# Display.net
KiCad netlist of a schematic drawn in Altium Designer
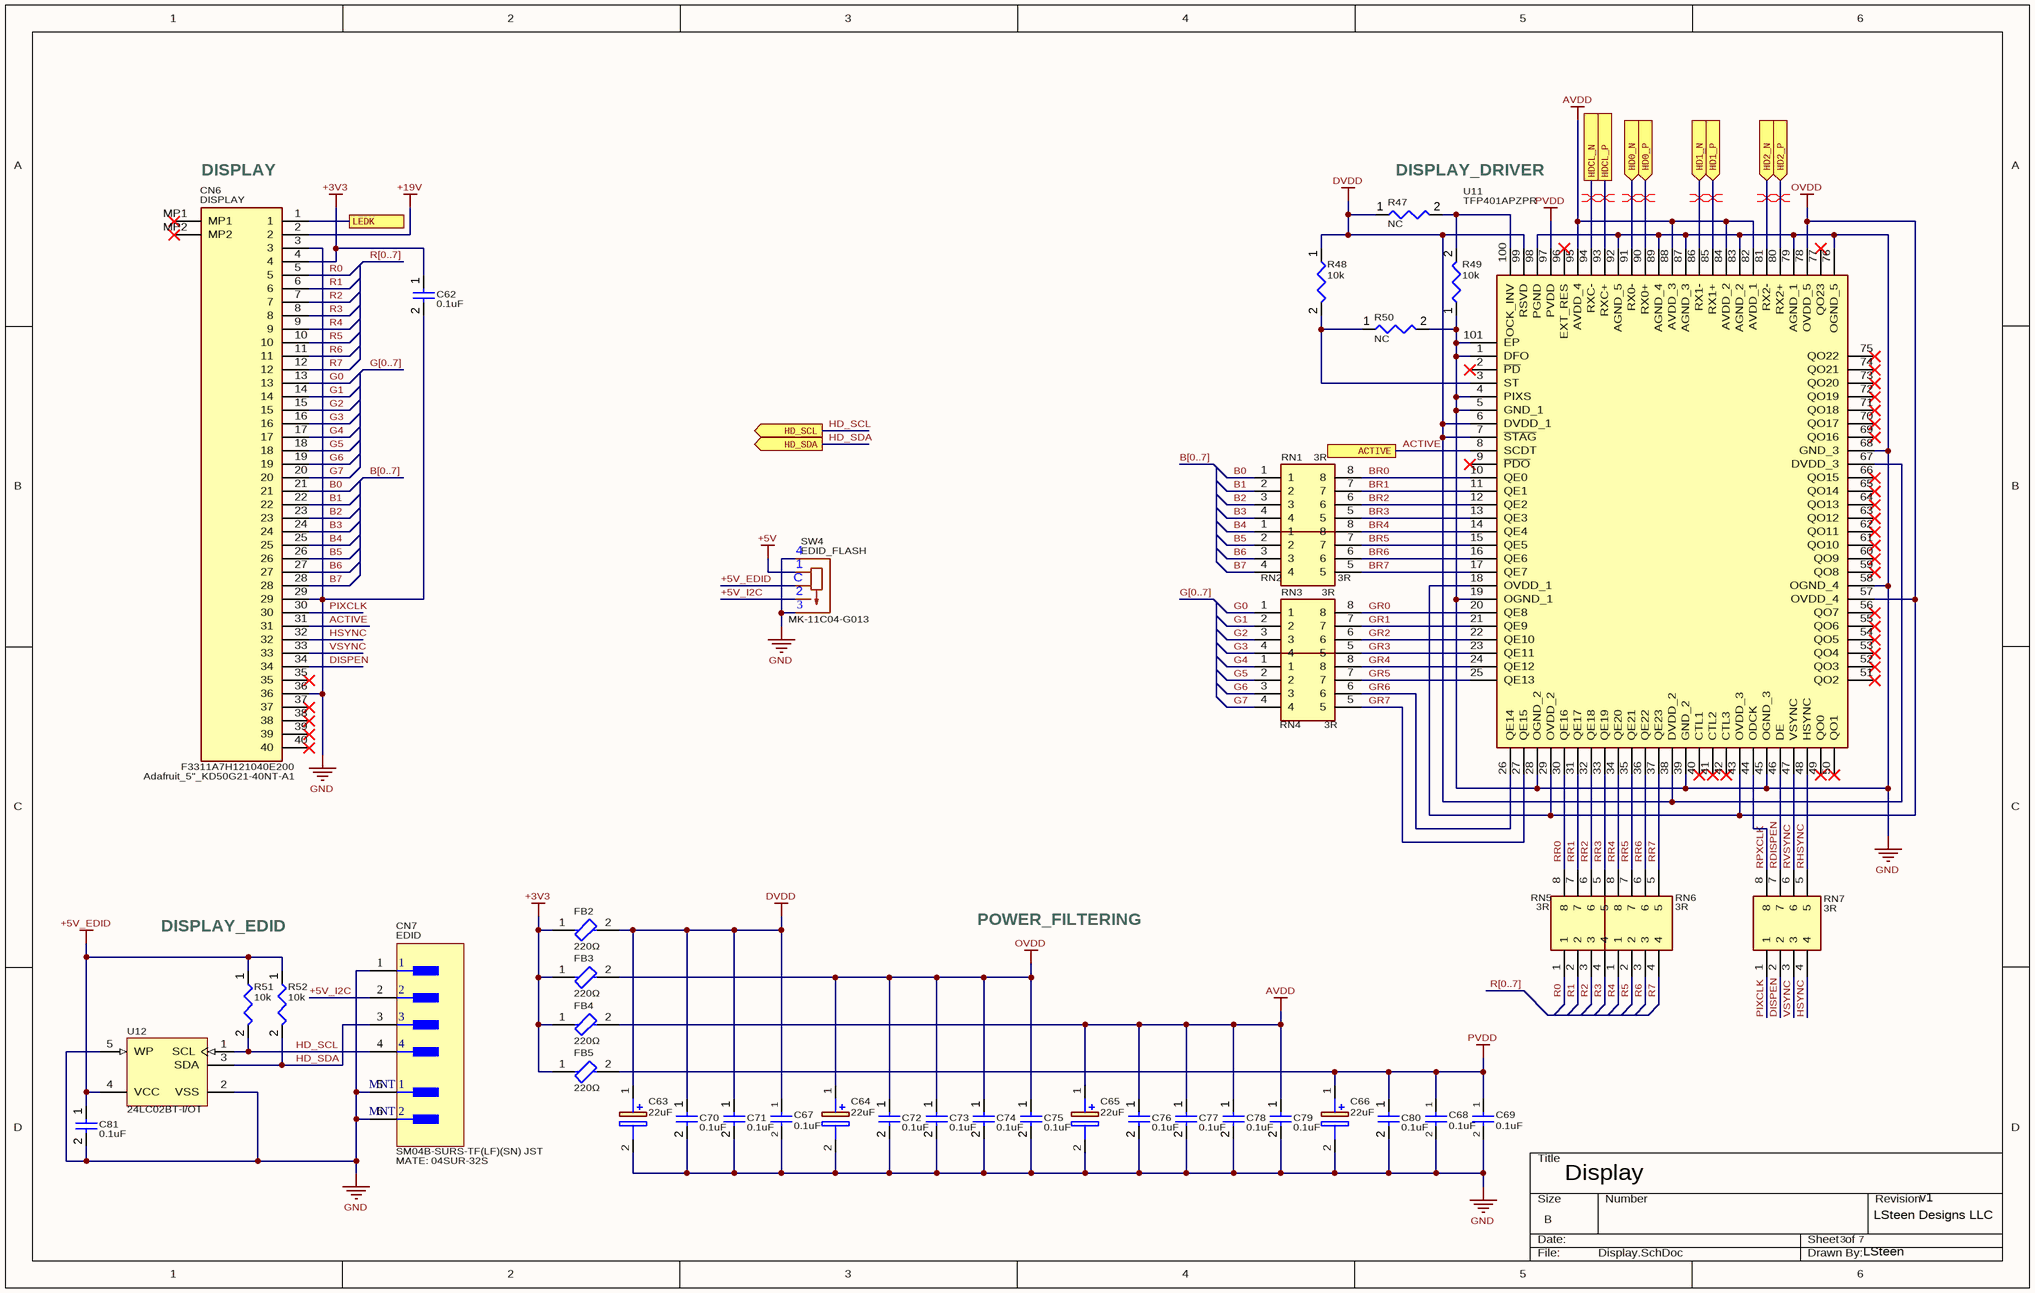
[diagram p0: Display.SchDoc]

(export (version "E")
  (design (tool "Eeschema 10.0.6"))
  (components
    (comp (ref "C62")
      (value "0.1uF")
      (footprint "CAPC1005X56X25LL10T15")
      (description "Chip Capacitor, 0.1 uF, +/- 5%, 16 V, 0402 (1005 Metric)")
      (fields (field (name "TOLERANCE") "5%"))
      (libsource (lib "Colorado Technical University") (part "CAP-NP-2"))
    )
    (comp (ref "C63")
      (value "22uF")
      (footprint "SamacSys:CAPPC2114X150N")
      (description "Capacitor Polarised")
      (fields
        (field (name "MANUFACTURER_PART_NUMBER") "TACR226K006XTA")
        (field (name "MOUSER PART NUMBER") "581-TACR226K006X")
      )
      (libsource (lib "SamacSys") (part "TACR226K006XTA"))
    )
    (comp (ref "C64")
      (value "22uF")
      (footprint "SamacSys:CAPPC2114X150N")
      (description "Capacitor Polarised")
      (fields
        (field (name "MANUFACTURER_PART_NUMBER") "TACR226K006XTA")
        (field (name "MOUSER PART NUMBER") "581-TACR226K006X")
      )
      (libsource (lib "SamacSys") (part "TACR226K006XTA"))
    )
    (comp (ref "C65")
      (value "22uF")
      (footprint "SamacSys:CAPPC2114X150N")
      (description "Capacitor Polarised")
      (fields
        (field (name "MANUFACTURER_PART_NUMBER") "TACR226K006XTA")
        (field (name "MOUSER PART NUMBER") "581-TACR226K006X")
      )
      (libsource (lib "SamacSys") (part "TACR226K006XTA"))
    )
    (comp (ref "C66")
      (value "22uF")
      (footprint "SamacSys:CAPPC2114X150N")
      (description "Capacitor Polarised")
      (fields
        (field (name "MANUFACTURER_PART_NUMBER") "TACR226K006XTA")
        (field (name "MOUSER PART NUMBER") "581-TACR226K006X")
      )
      (libsource (lib "SamacSys") (part "TACR226K006XTA"))
    )
    (comp (ref "C67")
      (value "0.1uF")
      (footprint "SamacSys:CAPC1005X55N")
      (description "C0402")
      (libsource (lib "SamacSys") (part "C0402"))
    )
    (comp (ref "C68")
      (value "0.1uF")
      (footprint "SamacSys:CAPC1005X55N")
      (description "C0402")
      (libsource (lib "SamacSys") (part "C0402"))
    )
    (comp (ref "C69")
      (value "0.1uF")
      (footprint "SamacSys:CAPC1005X55N")
      (description "C0402")
      (libsource (lib "SamacSys") (part "C0402"))
    )
    (comp (ref "C70")
      (value "0.1uF")
      (footprint "CAPC1005X56X25LL10T15")
      (description "Chip Capacitor, 0.1 uF, +/- 5%, 16 V, 0402 (1005 Metric)")
      (fields (field (name "TOLERANCE") "5%"))
      (libsource (lib "Colorado Technical University") (part "CAP-NP-2"))
    )
    (comp (ref "C71")
      (value "0.1uF")
      (footprint "CAPC1005X56X25LL10T15")
      (description "Chip Capacitor, 0.1 uF, +/- 5%, 16 V, 0402 (1005 Metric)")
      (fields (field (name "TOLERANCE") "5%"))
      (libsource (lib "Colorado Technical University") (part "CAP-NP-2"))
    )
    (comp (ref "C72")
      (value "0.1uF")
      (footprint "CAPC1005X56X25LL10T15")
      (description "Chip Capacitor, 0.1 uF, +/- 5%, 16 V, 0402 (1005 Metric)")
      (fields (field (name "TOLERANCE") "5%"))
      (libsource (lib "Colorado Technical University") (part "CAP-NP-2"))
    )
    (comp (ref "C73")
      (value "0.1uF")
      (footprint "CAPC1005X56X25LL10T15")
      (description "Chip Capacitor, 0.1 uF, +/- 5%, 16 V, 0402 (1005 Metric)")
      (fields (field (name "TOLERANCE") "5%"))
      (libsource (lib "Colorado Technical University") (part "CAP-NP-2"))
    )
    (comp (ref "C74")
      (value "0.1uF")
      (footprint "CAPC1005X56X25LL10T15")
      (description "Chip Capacitor, 0.1 uF, +/- 5%, 16 V, 0402 (1005 Metric)")
      (fields (field (name "TOLERANCE") "5%"))
      (libsource (lib "Colorado Technical University") (part "CAP-NP-2"))
    )
    (comp (ref "C75")
      (value "0.1uF")
      (footprint "CAPC1005X56X25LL10T15")
      (description "Chip Capacitor, 0.1 uF, +/- 5%, 16 V, 0402 (1005 Metric)")
      (fields (field (name "TOLERANCE") "5%"))
      (libsource (lib "Colorado Technical University") (part "CAP-NP-2"))
    )
    (comp (ref "C76")
      (value "0.1uF")
      (footprint "CAPC1005X56X25LL10T15")
      (description "Chip Capacitor, 0.1 uF, +/- 5%, 16 V, 0402 (1005 Metric)")
      (fields (field (name "TOLERANCE") "5%"))
      (libsource (lib "Colorado Technical University") (part "CAP-NP-2"))
    )
    (comp (ref "C77")
      (value "0.1uF")
      (footprint "CAPC1005X56X25LL10T15")
      (description "Chip Capacitor, 0.1 uF, +/- 5%, 16 V, 0402 (1005 Metric)")
      (fields (field (name "TOLERANCE") "5%"))
      (libsource (lib "Colorado Technical University") (part "CAP-NP-2"))
    )
    (comp (ref "C78")
      (value "0.1uF")
      (footprint "CAPC1005X56X25LL10T15")
      (description "Chip Capacitor, 0.1 uF, +/- 5%, 16 V, 0402 (1005 Metric)")
      (fields (field (name "TOLERANCE") "5%"))
      (libsource (lib "Colorado Technical University") (part "CAP-NP-2"))
    )
    (comp (ref "C79")
      (value "0.1uF")
      (footprint "CAPC1005X56X25LL10T15")
      (description "Chip Capacitor, 0.1 uF, +/- 5%, 16 V, 0402 (1005 Metric)")
      (fields (field (name "TOLERANCE") "5%"))
      (libsource (lib "Colorado Technical University") (part "CAP-NP-2"))
    )
    (comp (ref "C80")
      (value "0.1uF")
      (footprint "CAPC1005X56X25LL10T15")
      (description "Chip Capacitor, 0.1 uF, +/- 5%, 16 V, 0402 (1005 Metric)")
      (fields (field (name "TOLERANCE") "5%"))
      (libsource (lib "Colorado Technical University") (part "CAP-NP-2"))
    )
    (comp (ref "C81")
      (value "0.1uF")
      (footprint "CAPC1005X56X25LL10T15")
      (description "Chip Capacitor, 0.1 uF, +/- 5%, 16 V, 0402 (1005 Metric)")
      (fields (field (name "TOLERANCE") "5%"))
      (libsource (lib "Colorado Technical University") (part "CAP-NP-2"))
    )
    (comp (ref "CN6")
      (value "DISPLAY")
      (footprint "SamacSys:F3311A7H121040E200")
      (description "Connector")
      (fields (field (name "MANUFACTURER_PART_NUMBER") "F3311A7H121040E200"))
      (libsource (lib "*") (part "F3311A7H121040E200"))
    )
    (comp (ref "CN7")
      (value "EDID")
      (footprint "FP-SM04B-SURS-TF_LF_SN-MFG")
      (description "CONN HEADER SMD R/A 4POS 0.8MM")
      (libsource (lib "Altium Content Vault") (part "3b6f738a5616415d78381ad43816e4a"))
    )
    (comp (ref "FB2")
      (value "220Ω")
      (footprint "FP-BLM18-0_15-t0_5-IPC_B")
      (description "Chip Ferrite Bead, 0603, 220Ω @ 100MHz, 25%, 0.04Ω, 2.5A")
      (libsource (lib "Altium Content Vault") (part "5f30dd21d616792df468990f7003faa"))
    )
    (comp (ref "FB3")
      (value "220Ω")
      (footprint "FP-BLM18-0_15-t0_5-IPC_B")
      (description "Chip Ferrite Bead, 0603, 220Ω @ 100MHz, 25%, 0.04Ω, 2.5A")
      (libsource (lib "Altium Content Vault") (part "5f30dd21d616792df468990f7003faa"))
    )
    (comp (ref "FB4")
      (value "220Ω")
      (footprint "FP-BLM18-0_15-t0_5-IPC_B")
      (description "Chip Ferrite Bead, 0603, 220Ω @ 100MHz, 25%, 0.04Ω, 2.5A")
      (libsource (lib "Altium Content Vault") (part "5f30dd21d616792df468990f7003faa"))
    )
    (comp (ref "FB5")
      (value "220Ω")
      (footprint "FP-BLM18-0_15-t0_5-IPC_B")
      (description "Chip Ferrite Bead, 0603, 220Ω @ 100MHz, 25%, 0.04Ω, 2.5A")
      (libsource (lib "Altium Content Vault") (part "5f30dd21d616792df468990f7003faa"))
    )
    (comp (ref "R47")
      (value "NC")
      (footprint "RESC0402(1005)_L")
      (description "Chip Resistor, 0 Ohms, +/-5 %, 63 mW, -55 to 155 degC, 0402")
      (fields (field (name "TOLERANCE") "5%") (field (name "POWER") "63mW"))
      (libsource (lib "Colorado Technical University") (part "RES-2"))
    )
    (comp (ref "R48")
      (value "10k")
      (footprint "RESC0402(1005)_L")
      (description "Chip Resistor, 10 kOhms, +/-5 %, 63 mW, -55 to 155 degC, 0402")
      (fields (field (name "TOLERANCE") "5%") (field (name "POWER") "63mW"))
      (libsource (lib "Colorado Technical University") (part "RES-2"))
    )
    (comp (ref "R49")
      (value "10k")
      (footprint "RESC0402(1005)_L")
      (description "Chip Resistor, 10 kOhms, +/-5 %, 63 mW, -55 to 155 degC, 0402")
      (fields (field (name "TOLERANCE") "5%") (field (name "POWER") "63mW"))
      (libsource (lib "Colorado Technical University") (part "RES-2"))
    )
    (comp (ref "R50")
      (value "NC")
      (footprint "RESC0402(1005)_L")
      (description "Chip Resistor, 0 Ohms, +/-5 %, 63 mW, -55 to 155 degC, 0402")
      (fields (field (name "TOLERANCE") "5%") (field (name "POWER") "63mW"))
      (libsource (lib "Colorado Technical University") (part "RES-2"))
    )
    (comp (ref "R51")
      (value "10k")
      (footprint "RESC0402(1005)_L")
      (description "Chip Resistor, 10 kOhms, +/-5 %, 63 mW, -55 to 155 degC, 0402")
      (fields (field (name "TOLERANCE") "5%") (field (name "POWER") "63mW"))
      (libsource (lib "Colorado Technical University") (part "RES-2"))
    )
    (comp (ref "R52")
      (value "10k")
      (footprint "RESC0402(1005)_L")
      (description "Chip Resistor, 10 kOhms, +/-5 %, 63 mW, -55 to 155 degC, 0402")
      (fields (field (name "TOLERANCE") "5%") (field (name "POWER") "63mW"))
      (libsource (lib "Colorado Technical University") (part "RES-2"))
    )
    (comp (ref "RN1")
      (value "3R")
      (footprint "SamacSys:YC124JR0733RL")
      (description "Resistor Network")
      (fields
        (field (name "MANUFACTURER_PART_NUMBER") "YC124-JR-0733RL")
        (field (name "MOUSER PART NUMBER") "603-YC124-JR-0733RL")
      )
      (libsource (lib "SamacSys") (part "YC124-JR-073RL"))
    )
    (comp (ref "RN2")
      (value "3R")
      (footprint "SamacSys:YC124JR0733RL")
      (description "Resistor Network")
      (fields
        (field (name "MANUFACTURER_PART_NUMBER") "YC124-JR-0733RL")
        (field (name "MOUSER PART NUMBER") "603-YC124-JR-0733RL")
      )
      (libsource (lib "SamacSys") (part "YC124-JR-073RL"))
    )
    (comp (ref "RN3")
      (value "3R")
      (footprint "SamacSys:YC124JR0733RL")
      (description "Resistor Network")
      (fields
        (field (name "MANUFACTURER_PART_NUMBER") "YC124-JR-0733RL")
        (field (name "MOUSER PART NUMBER") "603-YC124-JR-0733RL")
      )
      (libsource (lib "SamacSys") (part "YC124-JR-073RL"))
    )
    (comp (ref "RN4")
      (value "3R")
      (footprint "SamacSys:YC124JR0733RL")
      (description "Resistor Network")
      (fields
        (field (name "MANUFACTURER_PART_NUMBER") "YC124-JR-0733RL")
        (field (name "MOUSER PART NUMBER") "603-YC124-JR-0733RL")
      )
      (libsource (lib "SamacSys") (part "YC124-JR-073RL"))
    )
    (comp (ref "RN5")
      (value "3R")
      (footprint "SamacSys:YC124JR0733RL")
      (description "Resistor Network")
      (fields
        (field (name "MANUFACTURER_PART_NUMBER") "YC124-JR-0733RL")
        (field (name "MOUSER PART NUMBER") "603-YC124-JR-0733RL")
      )
      (libsource (lib "") (part "YC124-JR-073RL_1"))
    )
    (comp (ref "RN6")
      (value "3R")
      (footprint "SamacSys:YC124JR0733RL")
      (description "Resistor Network")
      (fields
        (field (name "MANUFACTURER_PART_NUMBER") "YC124-JR-0733RL")
        (field (name "MOUSER PART NUMBER") "603-YC124-JR-0733RL")
      )
      (libsource (lib "") (part "YC124-JR-073RL_1"))
    )
    (comp (ref "RN7")
      (value "3R")
      (footprint "SamacSys:YC124JR0733RL")
      (description "Resistor Network")
      (fields
        (field (name "MANUFACTURER_PART_NUMBER") "YC124-JR-0733RL")
        (field (name "MOUSER PART NUMBER") "603-YC124-JR-0733RL")
      )
      (libsource (lib "") (part "YC124-JR-073RL_1"))
    )
    (comp (ref "SW4")
      (value "EDID_FLASH")
      (footprint "SW-SMD_MK-11C04-G013")
      (description "SPDT 1A 6V Slide Switch")
      (libsource (lib "Schlib1") (part "MK-11C04-G013"))
    )
    (comp (ref "U11")
      (value "TFP401APZPR")
      (footprint "SamacSys:QFP50P1600X1600X120-100N")
      (description "Integrated Circuit")
      (fields (field (name "MOUSER PART NUMBER") "595-TFP401APZPR"))
      (libsource (lib "SamacSys") (part "TFP401APZPR"))
    )
    (comp (ref "U12")
      (value "24LC02BT-I/OT")
      (footprint "SOT-23-OT5_L")
      (description "2Kbit, 400kHz, 2.5V, I2C Serial EEPROM, 5-Pin SOT-23, Industrial Temperature, Tape and Reel")
      (libsource (lib "Altium Content Vault") (part "MEM-SEEPROM-24AA16-OT-5"))
    )
  )
  (nets
    (net (code "1") (name "+3V3") (class "Default")
      (node (ref "C62") (pin "1") (pinfunction "1_1") (pintype "passive"))
      (node (ref "CN6") (pin "4") (pinfunction "4_4") (pintype "passive"))
      (node (ref "FB2") (pin "1") (pinfunction "1_1") (pintype "passive"))
      (node (ref "FB3") (pin "1") (pinfunction "1_1") (pintype "passive"))
      (node (ref "FB4") (pin "1") (pinfunction "1_1") (pintype "passive"))
      (node (ref "FB5") (pin "1") (pinfunction "1_1") (pintype "passive"))
    )
    (net (code "2") (name "+5V") (class "Default")
      (node (ref "SW4") (pin "1") (pinfunction "1_1") (pintype "power_in"))
    )
    (net (code "3") (name "+5V_EDID") (class "Default")
      (node (ref "C81") (pin "1") (pinfunction "1_1") (pintype "passive"))
      (node (ref "R51") (pin "1") (pinfunction "1_1") (pintype "passive"))
      (node (ref "R52") (pin "1") (pinfunction "1_1") (pintype "passive"))
      (node (ref "SW4") (pin "C") (pinfunction "C_C") (pintype "power_in"))
      (node (ref "U12") (pin "4") (pinfunction "VCC_4") (pintype "power_in"))
    )
    (net (code "4") (name "+19V") (class "Default")
      (node (ref "CN6") (pin "2") (pinfunction "2_2") (pintype "passive"))
    )
    (net (code "5") (name "/+5V_I2C") (class "Default")
      (node (ref "CN7") (pin "2") (pinfunction "2_2") (pintype "passive"))
      (node (ref "SW4") (pin "2") (pinfunction "2_2") (pintype "passive"))
    )
    (net (code "6") (name "/ACTIVE") (class "Default")
      (node (ref "CN6") (pin "31") (pinfunction "31_31") (pintype "passive"))
      (node (ref "U11") (pin "8") (pinfunction "SCDT_8") (pintype "passive"))
    )
    (net (code "7") (name "/B0") (class "Default")
      (node (ref "CN6") (pin "21") (pinfunction "21_21") (pintype "passive"))
      (node (ref "RN1") (pin "1") (pinfunction "1_1") (pintype "passive"))
    )
    (net (code "8") (name "/B1") (class "Default")
      (node (ref "CN6") (pin "22") (pinfunction "22_22") (pintype "passive"))
      (node (ref "RN1") (pin "2") (pinfunction "2_2") (pintype "passive"))
    )
    (net (code "9") (name "/B2") (class "Default")
      (node (ref "CN6") (pin "23") (pinfunction "23_23") (pintype "passive"))
      (node (ref "RN1") (pin "3") (pinfunction "3_3") (pintype "passive"))
    )
    (net (code "10") (name "/B3") (class "Default")
      (node (ref "CN6") (pin "24") (pinfunction "24_24") (pintype "passive"))
      (node (ref "RN1") (pin "4") (pinfunction "4_4") (pintype "passive"))
    )
    (net (code "11") (name "/B4") (class "Default")
      (node (ref "CN6") (pin "25") (pinfunction "25_25") (pintype "passive"))
      (node (ref "RN2") (pin "1") (pinfunction "1_1") (pintype "passive"))
    )
    (net (code "12") (name "/B5") (class "Default")
      (node (ref "CN6") (pin "26") (pinfunction "26_26") (pintype "passive"))
      (node (ref "RN2") (pin "2") (pinfunction "2_2") (pintype "passive"))
    )
    (net (code "13") (name "/B6") (class "Default")
      (node (ref "CN6") (pin "27") (pinfunction "27_27") (pintype "passive"))
      (node (ref "RN2") (pin "3") (pinfunction "3_3") (pintype "passive"))
    )
    (net (code "14") (name "/B7") (class "Default")
      (node (ref "CN6") (pin "28") (pinfunction "28_28") (pintype "passive"))
      (node (ref "RN2") (pin "4") (pinfunction "4_4") (pintype "passive"))
    )
    (net (code "15") (name "/BR0") (class "Default")
      (node (ref "RN1") (pin "8") (pinfunction "8_8") (pintype "passive"))
      (node (ref "U11") (pin "10") (pinfunction "QE0_10") (pintype "passive"))
    )
    (net (code "16") (name "/BR1") (class "Default")
      (node (ref "RN1") (pin "7") (pinfunction "7_7") (pintype "passive"))
      (node (ref "U11") (pin "11") (pinfunction "QE1_11") (pintype "passive"))
    )
    (net (code "17") (name "/BR2") (class "Default")
      (node (ref "RN1") (pin "6") (pinfunction "6_6") (pintype "passive"))
      (node (ref "U11") (pin "12") (pinfunction "QE2_12") (pintype "passive"))
    )
    (net (code "18") (name "/BR3") (class "Default")
      (node (ref "RN1") (pin "5") (pinfunction "5_5") (pintype "passive"))
      (node (ref "U11") (pin "13") (pinfunction "QE3_13") (pintype "passive"))
    )
    (net (code "19") (name "/BR4") (class "Default")
      (node (ref "RN2") (pin "8") (pinfunction "8_8") (pintype "passive"))
      (node (ref "U11") (pin "14") (pinfunction "QE4_14") (pintype "passive"))
    )
    (net (code "20") (name "/BR5") (class "Default")
      (node (ref "RN2") (pin "7") (pinfunction "7_7") (pintype "passive"))
      (node (ref "U11") (pin "15") (pinfunction "QE5_15") (pintype "passive"))
    )
    (net (code "21") (name "/BR6") (class "Default")
      (node (ref "RN2") (pin "6") (pinfunction "6_6") (pintype "passive"))
      (node (ref "U11") (pin "16") (pinfunction "QE6_16") (pintype "passive"))
    )
    (net (code "22") (name "/BR7") (class "Default")
      (node (ref "RN2") (pin "5") (pinfunction "5_5") (pintype "passive"))
      (node (ref "U11") (pin "17") (pinfunction "QE7_17") (pintype "passive"))
    )
    (net (code "24") (name "/DISPEN") (class "Default")
      (node (ref "CN6") (pin "34") (pinfunction "34_34") (pintype "passive"))
      (node (ref "RN7") (pin "2") (pinfunction "2_2") (pintype "passive"))
    )
    (net (code "25") (name "/G0") (class "Default")
      (node (ref "CN6") (pin "13") (pinfunction "13_13") (pintype "passive"))
      (node (ref "RN3") (pin "1") (pinfunction "1_1") (pintype "passive"))
    )
    (net (code "26") (name "/G1") (class "Default")
      (node (ref "CN6") (pin "14") (pinfunction "14_14") (pintype "passive"))
      (node (ref "RN3") (pin "2") (pinfunction "2_2") (pintype "passive"))
    )
    (net (code "27") (name "/G2") (class "Default")
      (node (ref "CN6") (pin "15") (pinfunction "15_15") (pintype "passive"))
      (node (ref "RN3") (pin "3") (pinfunction "3_3") (pintype "passive"))
    )
    (net (code "28") (name "/G3") (class "Default")
      (node (ref "CN6") (pin "16") (pinfunction "16_16") (pintype "passive"))
      (node (ref "RN3") (pin "4") (pinfunction "4_4") (pintype "passive"))
    )
    (net (code "29") (name "/G4") (class "Default")
      (node (ref "CN6") (pin "17") (pinfunction "17_17") (pintype "passive"))
      (node (ref "RN4") (pin "1") (pinfunction "1_1") (pintype "passive"))
    )
    (net (code "30") (name "/G5") (class "Default")
      (node (ref "CN6") (pin "18") (pinfunction "18_18") (pintype "passive"))
      (node (ref "RN4") (pin "2") (pinfunction "2_2") (pintype "passive"))
    )
    (net (code "31") (name "/G6") (class "Default")
      (node (ref "CN6") (pin "19") (pinfunction "19_19") (pintype "passive"))
      (node (ref "RN4") (pin "3") (pinfunction "3_3") (pintype "passive"))
    )
    (net (code "32") (name "/G7") (class "Default")
      (node (ref "CN6") (pin "20") (pinfunction "20_20") (pintype "passive"))
      (node (ref "RN4") (pin "4") (pinfunction "4_4") (pintype "passive"))
    )
    (net (code "33") (name "/GR0") (class "Default")
      (node (ref "RN3") (pin "8") (pinfunction "8_8") (pintype "passive"))
      (node (ref "U11") (pin "20") (pinfunction "QE8_20") (pintype "passive"))
    )
    (net (code "34") (name "/GR1") (class "Default")
      (node (ref "RN3") (pin "7") (pinfunction "7_7") (pintype "passive"))
      (node (ref "U11") (pin "21") (pinfunction "QE9_21") (pintype "passive"))
    )
    (net (code "35") (name "/GR2") (class "Default")
      (node (ref "RN3") (pin "6") (pinfunction "6_6") (pintype "passive"))
      (node (ref "U11") (pin "22") (pinfunction "QE10_22") (pintype "passive"))
    )
    (net (code "36") (name "/GR3") (class "Default")
      (node (ref "RN3") (pin "5") (pinfunction "5_5") (pintype "passive"))
      (node (ref "U11") (pin "23") (pinfunction "QE11_23") (pintype "passive"))
    )
    (net (code "37") (name "/GR4") (class "Default")
      (node (ref "RN4") (pin "8") (pinfunction "8_8") (pintype "passive"))
      (node (ref "U11") (pin "24") (pinfunction "QE12_24") (pintype "passive"))
    )
    (net (code "38") (name "/GR5") (class "Default")
      (node (ref "RN4") (pin "7") (pinfunction "7_7") (pintype "passive"))
      (node (ref "U11") (pin "25") (pinfunction "QE13_25") (pintype "passive"))
    )
    (net (code "39") (name "/GR6") (class "Default")
      (node (ref "RN4") (pin "6") (pinfunction "6_6") (pintype "passive"))
      (node (ref "U11") (pin "26") (pinfunction "QE14_26") (pintype "passive"))
    )
    (net (code "40") (name "/GR7") (class "Default")
      (node (ref "RN4") (pin "5") (pinfunction "5_5") (pintype "passive"))
      (node (ref "U11") (pin "27") (pinfunction "QE15_27") (pintype "passive"))
    )
    (net (code "42") (name "/HD0_N") (class "Default")
      (node (ref "U11") (pin "91") (pinfunction "RX0-_91") (pintype "passive"))
    )
    (net (code "43") (name "/HD0_P") (class "Default")
      (node (ref "U11") (pin "90") (pinfunction "RX0+_90") (pintype "passive"))
    )
    (net (code "44") (name "/HD1_N") (class "Default")
      (node (ref "U11") (pin "86") (pinfunction "RX1-_86") (pintype "passive"))
    )
    (net (code "45") (name "/HD1_P") (class "Default")
      (node (ref "U11") (pin "85") (pinfunction "RX1+_85") (pintype "passive"))
    )
    (net (code "46") (name "/HD2_N") (class "Default")
      (node (ref "U11") (pin "81") (pinfunction "RX2-_81") (pintype "passive"))
    )
    (net (code "47") (name "/HD2_P") (class "Default")
      (node (ref "U11") (pin "80") (pinfunction "RX2+_80") (pintype "passive"))
    )
    (net (code "48") (name "/HDCL_N") (class "Default")
      (node (ref "U11") (pin "94") (pinfunction "RXC-_94") (pintype "passive"))
    )
    (net (code "49") (name "/HDCL_P") (class "Default")
      (node (ref "U11") (pin "93") (pinfunction "RXC+_93") (pintype "passive"))
    )
    (net (code "50") (name "/HD_SCL") (class "Default")
      (node (ref "CN7") (pin "4") (pinfunction "4_4") (pintype "passive"))
      (node (ref "R51") (pin "2") (pinfunction "2_2") (pintype "passive"))
      (node (ref "U12") (pin "1") (pinfunction "SCL_1") (pintype "input"))
    )
    (net (code "51") (name "/HD_SDA") (class "Default")
      (node (ref "CN7") (pin "3") (pinfunction "3_3") (pintype "passive"))
      (node (ref "R52") (pin "2") (pinfunction "2_2") (pintype "passive"))
      (node (ref "U12") (pin "3") (pinfunction "SDA_3") (pintype "passive"))
    )
    (net (code "52") (name "/HSYNC") (class "Default")
      (node (ref "CN6") (pin "32") (pinfunction "32_32") (pintype "passive"))
      (node (ref "RN7") (pin "4") (pinfunction "4_4") (pintype "passive"))
    )
    (net (code "53") (name "/LEDK") (class "Default")
      (node (ref "CN6") (pin "1") (pinfunction "1_1") (pintype "passive"))
    )
    (net (code "54") (name "/PIXCLK") (class "Default")
      (node (ref "CN6") (pin "30") (pinfunction "30_30") (pintype "passive"))
      (node (ref "RN7") (pin "1") (pinfunction "1_1") (pintype "passive"))
    )
    (net (code "55") (name "/R0") (class "Default")
      (node (ref "CN6") (pin "5") (pinfunction "5_5") (pintype "passive"))
      (node (ref "RN5") (pin "1") (pinfunction "1_1") (pintype "passive"))
    )
    (net (code "56") (name "/R1") (class "Default")
      (node (ref "CN6") (pin "6") (pinfunction "6_6") (pintype "passive"))
      (node (ref "RN5") (pin "2") (pinfunction "2_2") (pintype "passive"))
    )
    (net (code "57") (name "/R2") (class "Default")
      (node (ref "CN6") (pin "7") (pinfunction "7_7") (pintype "passive"))
      (node (ref "RN5") (pin "3") (pinfunction "3_3") (pintype "passive"))
    )
    (net (code "58") (name "/R3") (class "Default")
      (node (ref "CN6") (pin "8") (pinfunction "8_8") (pintype "passive"))
      (node (ref "RN5") (pin "4") (pinfunction "4_4") (pintype "passive"))
    )
    (net (code "59") (name "/R4") (class "Default")
      (node (ref "CN6") (pin "9") (pinfunction "9_9") (pintype "passive"))
      (node (ref "RN6") (pin "1") (pinfunction "1_1") (pintype "passive"))
    )
    (net (code "60") (name "/R5") (class "Default")
      (node (ref "CN6") (pin "10") (pinfunction "10_10") (pintype "passive"))
      (node (ref "RN6") (pin "2") (pinfunction "2_2") (pintype "passive"))
    )
    (net (code "61") (name "/R6") (class "Default")
      (node (ref "CN6") (pin "11") (pinfunction "11_11") (pintype "passive"))
      (node (ref "RN6") (pin "3") (pinfunction "3_3") (pintype "passive"))
    )
    (net (code "62") (name "/R7") (class "Default")
      (node (ref "CN6") (pin "12") (pinfunction "12_12") (pintype "passive"))
      (node (ref "RN6") (pin "4") (pinfunction "4_4") (pintype "passive"))
    )
    (net (code "63") (name "/RDISPEN") (class "Default")
      (node (ref "RN7") (pin "7") (pinfunction "7_7") (pintype "passive"))
      (node (ref "U11") (pin "46") (pinfunction "DE_46") (pintype "passive"))
    )
    (net (code "64") (name "/RHSYNC") (class "Default")
      (node (ref "RN7") (pin "5") (pinfunction "5_5") (pintype "passive"))
      (node (ref "U11") (pin "48") (pinfunction "HSYNC_48") (pintype "passive"))
    )
    (net (code "65") (name "/RPXCLK") (class "Default")
      (node (ref "RN7") (pin "8") (pinfunction "8_8") (pintype "passive"))
      (node (ref "U11") (pin "44") (pinfunction "ODCK_44") (pintype "passive"))
    )
    (net (code "66") (name "/RR0") (class "Default")
      (node (ref "RN5") (pin "8") (pinfunction "8_8") (pintype "passive"))
      (node (ref "U11") (pin "30") (pinfunction "QE16_30") (pintype "passive"))
    )
    (net (code "67") (name "/RR1") (class "Default")
      (node (ref "RN5") (pin "7") (pinfunction "7_7") (pintype "passive"))
      (node (ref "U11") (pin "31") (pinfunction "QE17_31") (pintype "passive"))
    )
    (net (code "68") (name "/RR2") (class "Default")
      (node (ref "RN5") (pin "6") (pinfunction "6_6") (pintype "passive"))
      (node (ref "U11") (pin "32") (pinfunction "QE18_32") (pintype "passive"))
    )
    (net (code "69") (name "/RR3") (class "Default")
      (node (ref "RN5") (pin "5") (pinfunction "5_5") (pintype "passive"))
      (node (ref "U11") (pin "33") (pinfunction "QE19_33") (pintype "passive"))
    )
    (net (code "70") (name "/RR4") (class "Default")
      (node (ref "RN6") (pin "8") (pinfunction "8_8") (pintype "passive"))
      (node (ref "U11") (pin "34") (pinfunction "QE20_34") (pintype "passive"))
    )
    (net (code "71") (name "/RR5") (class "Default")
      (node (ref "RN6") (pin "7") (pinfunction "7_7") (pintype "passive"))
      (node (ref "U11") (pin "35") (pinfunction "QE21_35") (pintype "passive"))
    )
    (net (code "72") (name "/RR6") (class "Default")
      (node (ref "RN6") (pin "6") (pinfunction "6_6") (pintype "passive"))
      (node (ref "U11") (pin "36") (pinfunction "QE22_36") (pintype "passive"))
    )
    (net (code "73") (name "/RR7") (class "Default")
      (node (ref "RN6") (pin "5") (pinfunction "5_5") (pintype "passive"))
      (node (ref "U11") (pin "37") (pinfunction "QE23_37") (pintype "passive"))
    )
    (net (code "74") (name "/RVSYNC") (class "Default")
      (node (ref "RN7") (pin "6") (pinfunction "6_6") (pintype "passive"))
      (node (ref "U11") (pin "47") (pinfunction "VSYNC_47") (pintype "passive"))
    )
    (net (code "76") (name "/VSYNC") (class "Default")
      (node (ref "CN6") (pin "33") (pinfunction "33_33") (pintype "passive"))
      (node (ref "RN7") (pin "3") (pinfunction "3_3") (pintype "passive"))
    )
    (net (code "77") (name "AVDD") (class "Default")
      (node (ref "C65") (pin "1") (pinfunction "+_1") (pintype "passive"))
      (node (ref "C76") (pin "1") (pinfunction "1_1") (pintype "passive"))
      (node (ref "C77") (pin "1") (pinfunction "1_1") (pintype "passive"))
      (node (ref "C78") (pin "1") (pinfunction "1_1") (pintype "passive"))
      (node (ref "C79") (pin "1") (pinfunction "1_1") (pintype "passive"))
      (node (ref "FB4") (pin "2") (pinfunction "2_2") (pintype "passive"))
      (node (ref "U11") (pin "82") (pinfunction "AVDD_1_82") (pintype "passive"))
      (node (ref "U11") (pin "84") (pinfunction "AVDD_2_84") (pintype "passive"))
      (node (ref "U11") (pin "88") (pinfunction "AVDD_3_88") (pintype "passive"))
      (node (ref "U11") (pin "95") (pinfunction "AVDD_4_95") (pintype "passive"))
    )
    (net (code "78") (name "DVDD") (class "Default")
      (node (ref "C63") (pin "1") (pinfunction "+_1") (pintype "passive"))
      (node (ref "C67") (pin "1") (pinfunction "1_1") (pintype "passive"))
      (node (ref "C70") (pin "1") (pinfunction "1_1") (pintype "passive"))
      (node (ref "C71") (pin "1") (pinfunction "1_1") (pintype "passive"))
      (node (ref "FB2") (pin "2") (pinfunction "2_2") (pintype "passive"))
      (node (ref "R47") (pin "1") (pinfunction "1_1") (pintype "passive"))
      (node (ref "R48") (pin "1") (pinfunction "1_1") (pintype "passive"))
      (node (ref "U11") (pin "38") (pinfunction "DVDD_2_38") (pintype "passive"))
      (node (ref "U11") (pin "6") (pinfunction "DVDD_1_6") (pintype "passive"))
      (node (ref "U11") (pin "67") (pinfunction "DVDD_3_67") (pintype "passive"))
      (node (ref "U11") (pin "7") (pinfunction "~{STAG}_7") (pintype "passive"))
      (node (ref "U11") (pin "99") (pinfunction "RSVD_99") (pintype "passive"))
    )
    (net (code "79") (name "GND") (class "Default")
      (node (ref "C62") (pin "2") (pinfunction "2_2") (pintype "passive"))
      (node (ref "C63") (pin "2") (pinfunction "-_2") (pintype "passive"))
      (node (ref "C64") (pin "2") (pinfunction "-_2") (pintype "passive"))
      (node (ref "C65") (pin "2") (pinfunction "-_2") (pintype "passive"))
      (node (ref "C66") (pin "2") (pinfunction "-_2") (pintype "passive"))
      (node (ref "C67") (pin "2") (pinfunction "2_2") (pintype "passive"))
      (node (ref "C68") (pin "2") (pinfunction "2_2") (pintype "passive"))
      (node (ref "C69") (pin "2") (pinfunction "2_2") (pintype "passive"))
      (node (ref "C70") (pin "2") (pinfunction "2_2") (pintype "passive"))
      (node (ref "C71") (pin "2") (pinfunction "2_2") (pintype "passive"))
      (node (ref "C72") (pin "2") (pinfunction "2_2") (pintype "passive"))
      (node (ref "C73") (pin "2") (pinfunction "2_2") (pintype "passive"))
      (node (ref "C74") (pin "2") (pinfunction "2_2") (pintype "passive"))
      (node (ref "C75") (pin "2") (pinfunction "2_2") (pintype "passive"))
      (node (ref "C76") (pin "2") (pinfunction "2_2") (pintype "passive"))
      (node (ref "C77") (pin "2") (pinfunction "2_2") (pintype "passive"))
      (node (ref "C78") (pin "2") (pinfunction "2_2") (pintype "passive"))
      (node (ref "C79") (pin "2") (pinfunction "2_2") (pintype "passive"))
      (node (ref "C80") (pin "2") (pinfunction "2_2") (pintype "passive"))
      (node (ref "C81") (pin "2") (pinfunction "2_2") (pintype "passive"))
      (node (ref "CN6") (pin "29") (pinfunction "29_29") (pintype "passive"))
      (node (ref "CN6") (pin "3") (pinfunction "3_3") (pintype "passive"))
      (node (ref "CN6") (pin "36") (pinfunction "36_36") (pintype "passive"))
      (node (ref "CN7") (pin "1") (pinfunction "1_1") (pintype "passive"))
      (node (ref "CN7") (pin "5") (pinfunction "MNT_1_5") (pintype "passive"))
      (node (ref "CN7") (pin "6") (pinfunction "MNT_2_6") (pintype "passive"))
      (node (ref "R49") (pin "1") (pinfunction "1_1") (pintype "passive"))
      (node (ref "R50") (pin "2") (pinfunction "2_2") (pintype "passive"))
      (node (ref "SW4") (pin "3") (pinfunction "NC_3") (pintype "power_in"))
      (node (ref "SW4") (pin "4") (pinfunction "4_4") (pintype "power_in"))
      (node (ref "U11") (pin "1") (pinfunction "DFO_1") (pintype "passive"))
      (node (ref "U11") (pin "101") (pinfunction "EP_101") (pintype "passive"))
      (node (ref "U11") (pin "19") (pinfunction "OGND_1_19") (pintype "passive"))
      (node (ref "U11") (pin "28") (pinfunction "OGND_2_28") (pintype "passive"))
      (node (ref "U11") (pin "39") (pinfunction "GND_2_39") (pintype "passive"))
      (node (ref "U11") (pin "4") (pinfunction "PIXS_4") (pintype "passive"))
      (node (ref "U11") (pin "45") (pinfunction "OGND_3_45") (pintype "passive"))
      (node (ref "U11") (pin "5") (pinfunction "GND_1_5") (pintype "passive"))
      (node (ref "U11") (pin "58") (pinfunction "OGND_4_58") (pintype "passive"))
      (node (ref "U11") (pin "68") (pinfunction "GND_3_68") (pintype "passive"))
      (node (ref "U11") (pin "76") (pinfunction "OGND_5_76") (pintype "passive"))
      (node (ref "U11") (pin "79") (pinfunction "AGND_1_79") (pintype "passive"))
      (node (ref "U11") (pin "83") (pinfunction "AGND_2_83") (pintype "passive"))
      (node (ref "U11") (pin "87") (pinfunction "AGND_3_87") (pintype "passive"))
      (node (ref "U11") (pin "89") (pinfunction "AGND_4_89") (pintype "passive"))
      (node (ref "U11") (pin "92") (pinfunction "AGND_5_92") (pintype "passive"))
      (node (ref "U11") (pin "98") (pinfunction "PGND_98") (pintype "passive"))
      (node (ref "U12") (pin "2") (pinfunction "VSS_2") (pintype "power_in"))
      (node (ref "U12") (pin "5") (pinfunction "WP_5") (pintype "input"))
    )
    (net (code "80") (name "Net-(U11-OCK_INV)") (class "Default")
      (node (ref "R47") (pin "2") (pinfunction "2_2") (pintype "passive"))
      (node (ref "R49") (pin "2") (pinfunction "2_2") (pintype "passive"))
      (node (ref "U11") (pin "100") (pinfunction "OCK_INV_100") (pintype "passive"))
    )
    (net (code "81") (name "Net-(U11-ST)") (class "Default")
      (node (ref "R48") (pin "2") (pinfunction "2_2") (pintype "passive"))
      (node (ref "R50") (pin "1") (pinfunction "1_1") (pintype "passive"))
      (node (ref "U11") (pin "3") (pinfunction "ST_3") (pintype "passive"))
    )
    (net (code "82") (name "OVDD") (class "Default")
      (node (ref "C64") (pin "1") (pinfunction "+_1") (pintype "passive"))
      (node (ref "C72") (pin "1") (pinfunction "1_1") (pintype "passive"))
      (node (ref "C73") (pin "1") (pinfunction "1_1") (pintype "passive"))
      (node (ref "C74") (pin "1") (pinfunction "1_1") (pintype "passive"))
      (node (ref "C75") (pin "1") (pinfunction "1_1") (pintype "passive"))
      (node (ref "FB3") (pin "2") (pinfunction "2_2") (pintype "passive"))
      (node (ref "U11") (pin "18") (pinfunction "OVDD_1_18") (pintype "passive"))
      (node (ref "U11") (pin "29") (pinfunction "OVDD_2_29") (pintype "passive"))
      (node (ref "U11") (pin "43") (pinfunction "OVDD_3_43") (pintype "passive"))
      (node (ref "U11") (pin "57") (pinfunction "OVDD_4_57") (pintype "passive"))
      (node (ref "U11") (pin "78") (pinfunction "OVDD_5_78") (pintype "passive"))
    )
    (net (code "83") (name "PVDD") (class "Default")
      (node (ref "C66") (pin "1") (pinfunction "+_1") (pintype "passive"))
      (node (ref "C68") (pin "1") (pinfunction "1_1") (pintype "passive"))
      (node (ref "C69") (pin "1") (pinfunction "1_1") (pintype "passive"))
      (node (ref "C80") (pin "1") (pinfunction "1_1") (pintype "passive"))
      (node (ref "FB5") (pin "2") (pinfunction "2_2") (pintype "passive"))
      (node (ref "U11") (pin "97") (pinfunction "PVDD_97") (pintype "passive"))
    )
    (net (code "84") (name "unconnected-(CN6-Pad35)") (class "Default")
      (node (ref "CN6") (pin "35") (pinfunction "35_35") (pintype "passive+no_connect"))
    )
    (net (code "85") (name "unconnected-(CN6-Pad37)") (class "Default")
      (node (ref "CN6") (pin "37") (pinfunction "37_37") (pintype "passive+no_connect"))
    )
    (net (code "86") (name "unconnected-(CN6-Pad38)") (class "Default")
      (node (ref "CN6") (pin "38") (pinfunction "38_38") (pintype "passive+no_connect"))
    )
    (net (code "87") (name "unconnected-(CN6-Pad39)") (class "Default")
      (node (ref "CN6") (pin "39") (pinfunction "39_39") (pintype "passive+no_connect"))
    )
    (net (code "88") (name "unconnected-(CN6-Pad40)") (class "Default")
      (node (ref "CN6") (pin "40") (pinfunction "40_40") (pintype "passive+no_connect"))
    )
    (net (code "89") (name "unconnected-(CN6-PadMP1)") (class "Default")
      (node (ref "CN6") (pin "MP1") (pinfunction "MP1_MP1") (pintype "passive+no_connect"))
    )
    (net (code "90") (name "unconnected-(CN6-PadMP2)") (class "Default")
      (node (ref "CN6") (pin "MP2") (pinfunction "MP2_MP2") (pintype "passive+no_connect"))
    )
    (net (code "91") (name "unconnected-(U11-CTL1-Pad40)") (class "Default")
      (node (ref "U11") (pin "40") (pinfunction "CTL1_40") (pintype "passive+no_connect"))
    )
    (net (code "92") (name "unconnected-(U11-CTL2-Pad41)") (class "Default")
      (node (ref "U11") (pin "41") (pinfunction "CTL2_41") (pintype "passive+no_connect"))
    )
    (net (code "93") (name "unconnected-(U11-CTL3-Pad42)") (class "Default")
      (node (ref "U11") (pin "42") (pinfunction "CTL3_42") (pintype "passive+no_connect"))
    )
    (net (code "94") (name "unconnected-(U11-EXT_RES-Pad96)") (class "Default")
      (node (ref "U11") (pin "96") (pinfunction "EXT_RES_96") (pintype "passive+no_connect"))
    )
    (net (code "95") (name "unconnected-(U11-QO0-Pad49)") (class "Default")
      (node (ref "U11") (pin "49") (pinfunction "QO0_49") (pintype "passive+no_connect"))
    )
    (net (code "96") (name "unconnected-(U11-QO1-Pad50)") (class "Default")
      (node (ref "U11") (pin "50") (pinfunction "QO1_50") (pintype "passive+no_connect"))
    )
    (net (code "97") (name "unconnected-(U11-QO2-Pad51)") (class "Default")
      (node (ref "U11") (pin "51") (pinfunction "QO2_51") (pintype "passive+no_connect"))
    )
    (net (code "98") (name "unconnected-(U11-QO3-Pad52)") (class "Default")
      (node (ref "U11") (pin "52") (pinfunction "QO3_52") (pintype "passive+no_connect"))
    )
    (net (code "99") (name "unconnected-(U11-QO4-Pad53)") (class "Default")
      (node (ref "U11") (pin "53") (pinfunction "QO4_53") (pintype "passive+no_connect"))
    )
    (net (code "100") (name "unconnected-(U11-QO5-Pad54)") (class "Default")
      (node (ref "U11") (pin "54") (pinfunction "QO5_54") (pintype "passive+no_connect"))
    )
    (net (code "101") (name "unconnected-(U11-QO6-Pad55)") (class "Default")
      (node (ref "U11") (pin "55") (pinfunction "QO6_55") (pintype "passive+no_connect"))
    )
    (net (code "102") (name "unconnected-(U11-QO7-Pad56)") (class "Default")
      (node (ref "U11") (pin "56") (pinfunction "QO7_56") (pintype "passive+no_connect"))
    )
    (net (code "103") (name "unconnected-(U11-QO8-Pad59)") (class "Default")
      (node (ref "U11") (pin "59") (pinfunction "QO8_59") (pintype "passive+no_connect"))
    )
    (net (code "104") (name "unconnected-(U11-QO9-Pad60)") (class "Default")
      (node (ref "U11") (pin "60") (pinfunction "QO9_60") (pintype "passive+no_connect"))
    )
    (net (code "105") (name "unconnected-(U11-QO10-Pad61)") (class "Default")
      (node (ref "U11") (pin "61") (pinfunction "QO10_61") (pintype "passive+no_connect"))
    )
    (net (code "106") (name "unconnected-(U11-QO11-Pad62)") (class "Default")
      (node (ref "U11") (pin "62") (pinfunction "QO11_62") (pintype "passive+no_connect"))
    )
    (net (code "107") (name "unconnected-(U11-QO12-Pad63)") (class "Default")
      (node (ref "U11") (pin "63") (pinfunction "QO12_63") (pintype "passive+no_connect"))
    )
    (net (code "108") (name "unconnected-(U11-QO13-Pad64)") (class "Default")
      (node (ref "U11") (pin "64") (pinfunction "QO13_64") (pintype "passive+no_connect"))
    )
    (net (code "109") (name "unconnected-(U11-QO14-Pad65)") (class "Default")
      (node (ref "U11") (pin "65") (pinfunction "QO14_65") (pintype "passive+no_connect"))
    )
    (net (code "110") (name "unconnected-(U11-QO15-Pad66)") (class "Default")
      (node (ref "U11") (pin "66") (pinfunction "QO15_66") (pintype "passive+no_connect"))
    )
    (net (code "111") (name "unconnected-(U11-QO16-Pad69)") (class "Default")
      (node (ref "U11") (pin "69") (pinfunction "QO16_69") (pintype "passive+no_connect"))
    )
    (net (code "112") (name "unconnected-(U11-QO17-Pad70)") (class "Default")
      (node (ref "U11") (pin "70") (pinfunction "QO17_70") (pintype "passive+no_connect"))
    )
    (net (code "113") (name "unconnected-(U11-QO18-Pad71)") (class "Default")
      (node (ref "U11") (pin "71") (pinfunction "QO18_71") (pintype "passive+no_connect"))
    )
    (net (code "114") (name "unconnected-(U11-QO19-Pad72)") (class "Default")
      (node (ref "U11") (pin "72") (pinfunction "QO19_72") (pintype "passive+no_connect"))
    )
    (net (code "115") (name "unconnected-(U11-QO20-Pad73)") (class "Default")
      (node (ref "U11") (pin "73") (pinfunction "QO20_73") (pintype "passive+no_connect"))
    )
    (net (code "116") (name "unconnected-(U11-QO21-Pad74)") (class "Default")
      (node (ref "U11") (pin "74") (pinfunction "QO21_74") (pintype "passive+no_connect"))
    )
    (net (code "117") (name "unconnected-(U11-QO22-Pad75)") (class "Default")
      (node (ref "U11") (pin "75") (pinfunction "QO22_75") (pintype "passive+no_connect"))
    )
    (net (code "118") (name "unconnected-(U11-QO23-Pad77)") (class "Default")
      (node (ref "U11") (pin "77") (pinfunction "QO23_77") (pintype "passive+no_connect"))
    )
    (net (code "119") (name "unconnected-(U11-~{PDO}-Pad9)") (class "Default")
      (node (ref "U11") (pin "9") (pinfunction "~{PDO}_9") (pintype "passive+no_connect"))
    )
    (net (code "120") (name "unconnected-(U11-~{PD}-Pad2)") (class "Default")
      (node (ref "U11") (pin "2") (pinfunction "~{PD}_2") (pintype "passive+no_connect"))
    )
  )
)
